# Akkucheck.net
KiCad netlist of a schematic drawn in EAGLE
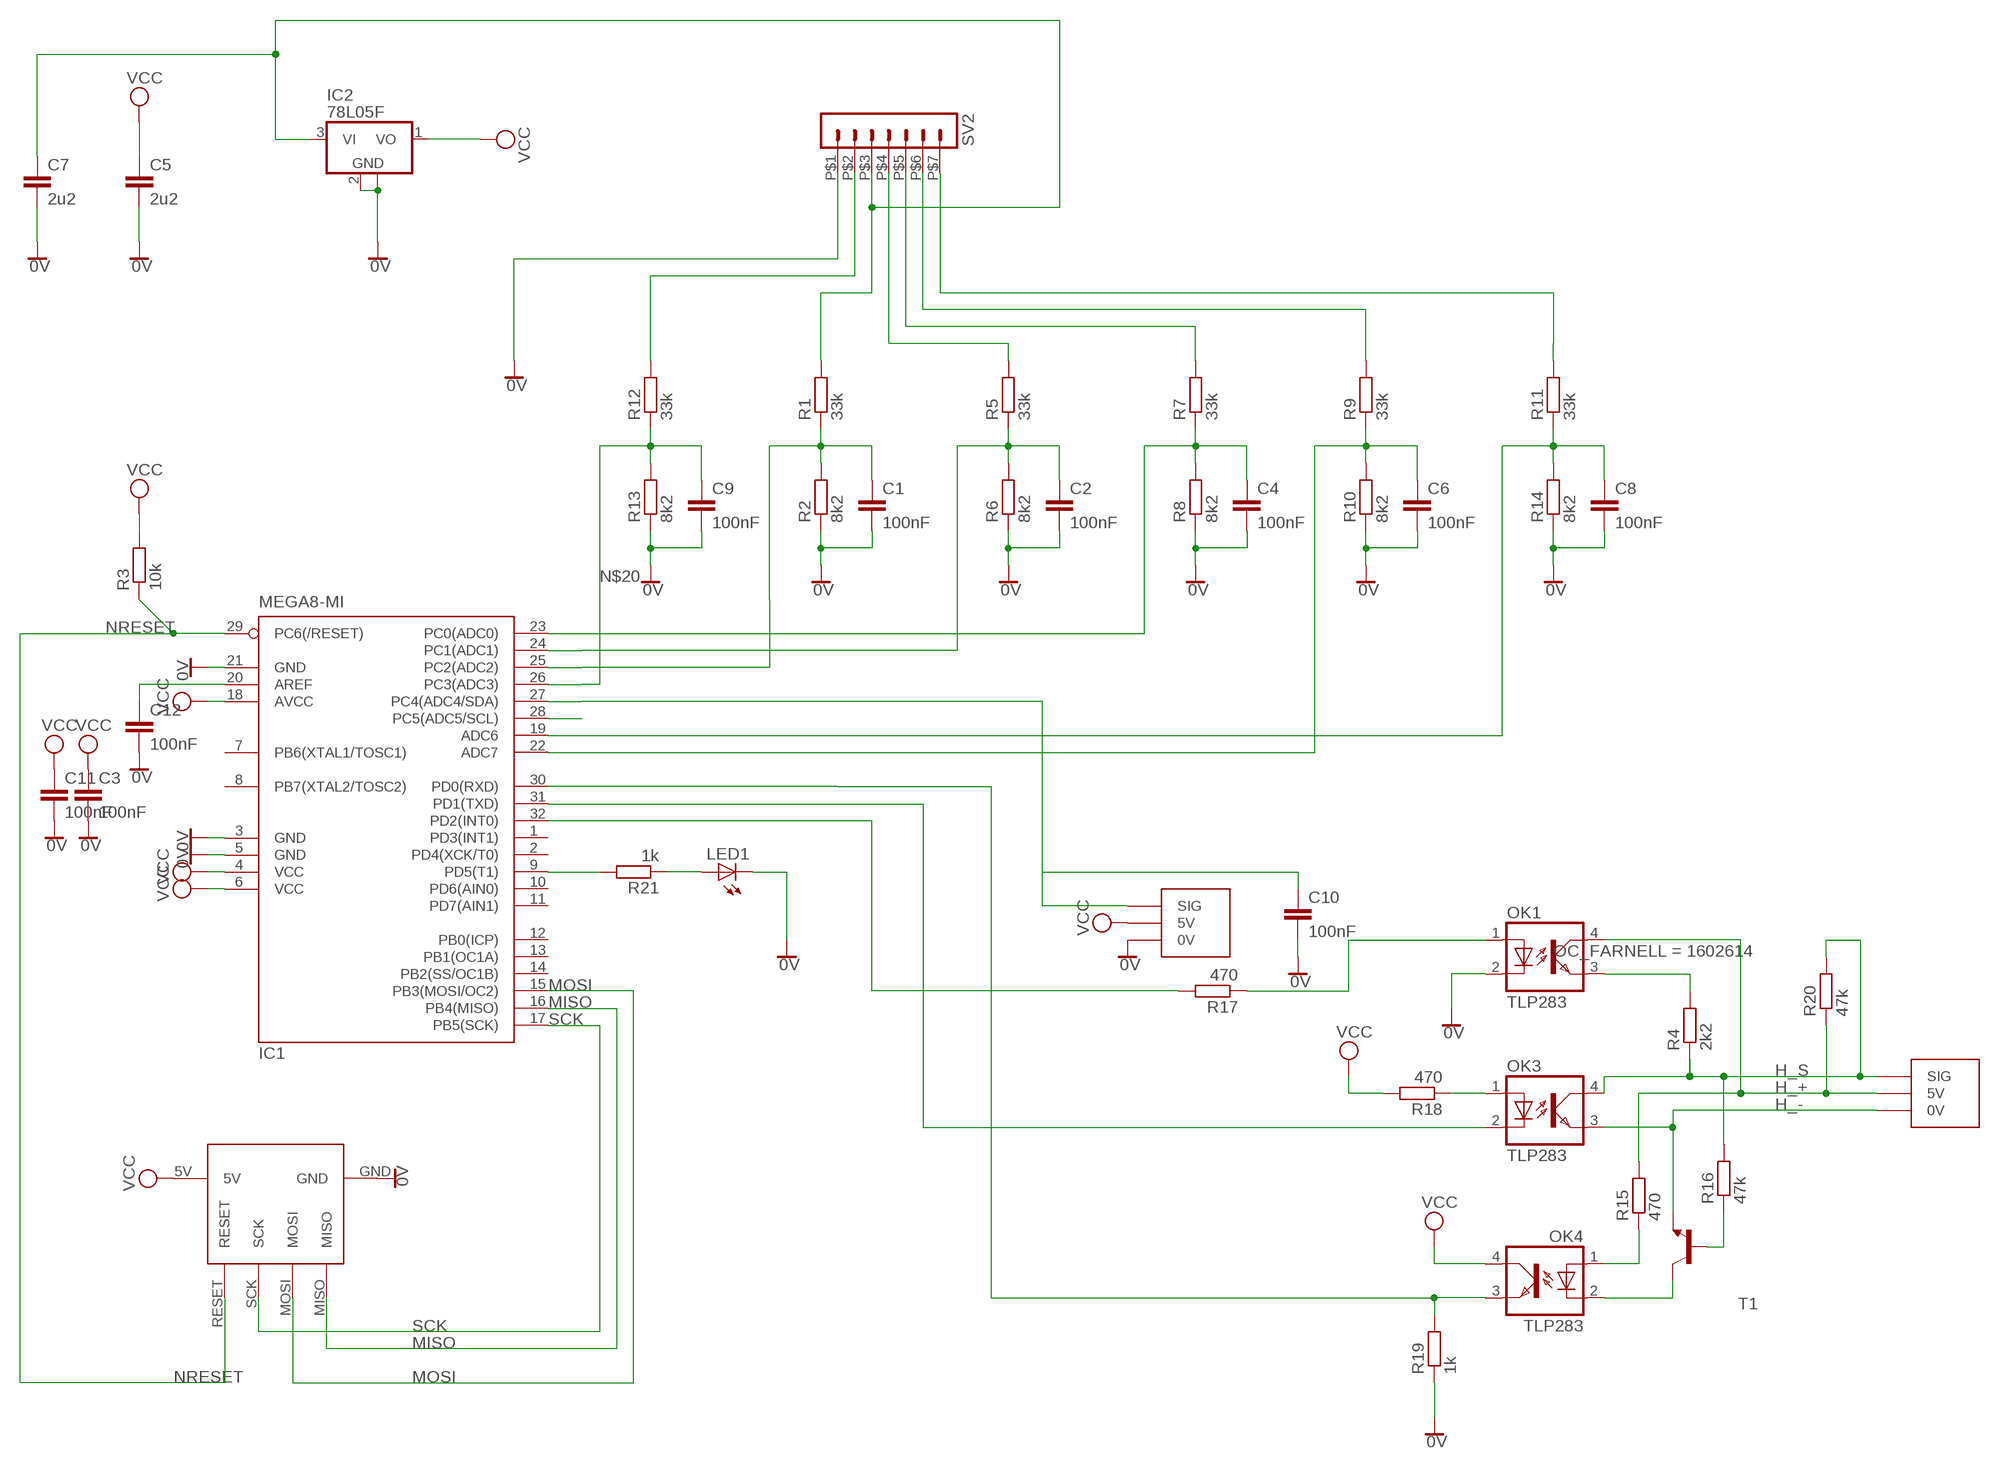
[diagram p0: schematic, sheet 1]

(export (version "E")
  (design (tool "Eeschema 10.0.6"))
  (components
    (comp (ref "C1")
      (value "100nF")
      (footprint "eagle-import:C0402")
      (fields (field (name "MF") "AVX") (field (name "MPN") "04023C104KAT2A"))
      (libsource (lib "eagle-import") (part "C-EUC0402"))
    )
    (comp (ref "C2")
      (value "100nF")
      (footprint "eagle-import:C0402")
      (fields (field (name "MF") "AVX") (field (name "MPN") "04023C104KAT2A"))
      (libsource (lib "eagle-import") (part "C-EUC0402"))
    )
    (comp (ref "C3")
      (value "100nF")
      (footprint "eagle-import:C0402")
      (fields (field (name "MF") "AVX") (field (name "MPN") "04023C104KAT2A"))
      (libsource (lib "eagle-import") (part "C-EUC0402"))
    )
    (comp (ref "C4")
      (value "100nF")
      (footprint "eagle-import:C0402")
      (fields (field (name "MF") "AVX") (field (name "MPN") "04023C104KAT2A"))
      (libsource (lib "eagle-import") (part "C-EUC0402"))
    )
    (comp (ref "C5")
      (value "2u2")
      (footprint "eagle-import:C0805")
      (fields (field (name "MF") "MULTICOMP") (field (name "MPN") "MC0805B225K250CT"))
      (libsource (lib "eagle-import") (part "C-EUC0805"))
    )
    (comp (ref "C6")
      (value "100nF")
      (footprint "eagle-import:C0402")
      (fields (field (name "MF") "AVX") (field (name "MPN") "04023C104KAT2A"))
      (libsource (lib "eagle-import") (part "C-EUC0402"))
    )
    (comp (ref "C7")
      (value "2u2")
      (footprint "eagle-import:C0805")
      (fields (field (name "MF") "MULTICOMP") (field (name "MPN") "MC0805B225K250CT"))
      (libsource (lib "eagle-import") (part "C-EUC0805"))
    )
    (comp (ref "C8")
      (value "100nF")
      (footprint "eagle-import:C0402")
      (fields (field (name "MF") "AVX") (field (name "MPN") "04023C104KAT2A"))
      (libsource (lib "eagle-import") (part "C-EUC0402"))
    )
    (comp (ref "C9")
      (value "100nF")
      (footprint "eagle-import:C0402")
      (fields (field (name "MF") "AVX") (field (name "MPN") "04023C104KAT2A"))
      (libsource (lib "eagle-import") (part "C-EUC0402"))
    )
    (comp (ref "C10")
      (value "100nF")
      (footprint "eagle-import:C0402")
      (fields (field (name "MF") "AVX") (field (name "MPN") "04023C104KAT2A"))
      (libsource (lib "eagle-import") (part "C-EUC0402"))
    )
    (comp (ref "C11")
      (value "100nF")
      (footprint "eagle-import:C0402")
      (fields (field (name "MF") "AVX") (field (name "MPN") "04023C104KAT2A"))
      (libsource (lib "eagle-import") (part "C-EUC0402"))
    )
    (comp (ref "C12")
      (value "100nF")
      (footprint "eagle-import:C0402")
      (fields (field (name "MF") "AVX") (field (name "MPN") "04023C104KAT2A"))
      (libsource (lib "eagle-import") (part "C-EUC0402"))
    )
    (comp (ref "IC1")
      (value "MEGA8-MI")
      (footprint "eagle-import:MLF32")
      (fields (field (name "MPN") "ATMEGA88PA-MU") (field (name "MF") "ATMEL"))
      (libsource (lib "eagle-import") (part "MEGA8-MI"))
    )
    (comp (ref "IC2")
      (value "78L05F")
      (footprint "eagle-import:SOT89")
      (fields (field (name "MF") "STMICROELECTRONICS") (field (name "MPN") "L78L05ABUTR"))
      (libsource (lib "eagle-import") (part "78LF05"))
    )
    (comp (ref "IN1")
      (value "3-WIRE_CONNWIRE")
      (footprint "eagle-import:3WIRE_CONN")
      (libsource (lib "eagle-import") (part "3-WIRE_CONNWIRE"))
    )
    (comp (ref "IN3")
      (value "3-WIRE_CONNWIRE")
      (footprint "eagle-import:3WIRE_CONN")
      (libsource (lib "eagle-import") (part "3-WIRE_CONNWIRE"))
    )
    (comp (ref "LED1")
      (value "LEDCHIPLED_0603")
      (footprint "eagle-import:CHIPLED_0603")
      (libsource (lib "eagle-import") (part "LEDCHIPLED_0603"))
    )
    (comp (ref "OK1")
      (value "TLP283")
      (footprint "eagle-import:MINI-FLAT-4")
      (fields
        (field (name "OC_FARNELL") "unknown")
        (field (name "MF") "AVAGO TECHNOLOGIES")
        (field (name "MPN") "ACPL-217-500E")
        (field (name "OC_FARNELL_1") "1602614")
      )
      (libsource (lib "eagle-import") (part "TLP283"))
    )
    (comp (ref "OK3")
      (value "TLP283")
      (footprint "eagle-import:MINI-FLAT-4")
      (fields
        (field (name "MF") "AVAGO TECHNOLOGIES")
        (field (name "MPN") "ACPL-217-500E")
        (field (name "OC_FARNELL") "1602614")
      )
      (libsource (lib "eagle-import") (part "TLP283"))
    )
    (comp (ref "OK4")
      (value "TLP283")
      (footprint "eagle-import:MINI-FLAT-4")
      (fields
        (field (name "MF") "AVAGO TECHNOLOGIES")
        (field (name "MPN") "ACPL-217-500E")
        (field (name "OC_FARNELL") "1602614")
      )
      (libsource (lib "eagle-import") (part "TLP283"))
    )
    (comp (ref "R1")
      (value "33k")
      (footprint "eagle-import:R0402")
      (fields (field (name "MF") "TE CONNECTIVITY") (field (name "MPN") "CRG0402F33K"))
      (libsource (lib "eagle-import") (part "R-EU_R0402"))
    )
    (comp (ref "R2")
      (value "8k2")
      (footprint "eagle-import:R0402")
      (fields (field (name "MF") "TE CONNECTIVITY") (field (name "MPN") "CRG0402F8K2"))
      (libsource (lib "eagle-import") (part "R-EU_R0402"))
    )
    (comp (ref "R3")
      (value "10k")
      (footprint "eagle-import:R0402")
      (fields (field (name "MF") "VISHAY DRALORIC") (field (name "MPN") "CRCW040210K0FKEAHP"))
      (libsource (lib "eagle-import") (part "R-EU_R0402"))
    )
    (comp (ref "R4")
      (value "2k2")
      (footprint "eagle-import:R0402")
      (fields (field (name "MF") "PANASONIC ELECTRONIC COMPONENTS") (field (name "MPN") "ERJ2GEJ222X"))
      (libsource (lib "eagle-import") (part "R-EU_R0402"))
    )
    (comp (ref "R5")
      (value "33k")
      (footprint "eagle-import:R0402")
      (fields (field (name "MF") "TE CONNECTIVITY") (field (name "MPN") "CRG0402F33K"))
      (libsource (lib "eagle-import") (part "R-EU_R0402"))
    )
    (comp (ref "R6")
      (value "8k2")
      (footprint "eagle-import:R0402")
      (fields (field (name "MF") "TE CONNECTIVITY") (field (name "MPN") "CRG0402F8K2"))
      (libsource (lib "eagle-import") (part "R-EU_R0402"))
    )
    (comp (ref "R7")
      (value "33k")
      (footprint "eagle-import:R0402")
      (fields (field (name "MF") "TE CONNECTIVITY") (field (name "MPN") "CRG0402F33K"))
      (libsource (lib "eagle-import") (part "R-EU_R0402"))
    )
    (comp (ref "R8")
      (value "8k2")
      (footprint "eagle-import:R0402")
      (fields (field (name "MF") "TE CONNECTIVITY") (field (name "MPN") "CRG0402F8K2"))
      (libsource (lib "eagle-import") (part "R-EU_R0402"))
    )
    (comp (ref "R9")
      (value "33k")
      (footprint "eagle-import:R0402")
      (fields (field (name "MF") "TE CONNECTIVITY") (field (name "MPN") "CRG0402F33K"))
      (libsource (lib "eagle-import") (part "R-EU_R0402"))
    )
    (comp (ref "R10")
      (value "8k2")
      (footprint "eagle-import:R0402")
      (fields (field (name "MF") "TE CONNECTIVITY") (field (name "MPN") "CRG0402F8K2"))
      (libsource (lib "eagle-import") (part "R-EU_R0402"))
    )
    (comp (ref "R11")
      (value "33k")
      (footprint "eagle-import:R0402")
      (fields (field (name "MF") "TE CONNECTIVITY") (field (name "MPN") "CRG0402F33K"))
      (libsource (lib "eagle-import") (part "R-EU_R0402"))
    )
    (comp (ref "R12")
      (value "33k")
      (footprint "eagle-import:R0402")
      (fields (field (name "MF") "TE CONNECTIVITY") (field (name "MPN") "CRG0402F33K"))
      (libsource (lib "eagle-import") (part "R-EU_R0402"))
    )
    (comp (ref "R13")
      (value "8k2")
      (footprint "eagle-import:R0402")
      (fields (field (name "MF") "TE CONNECTIVITY") (field (name "MPN") "CRG0402F8K2"))
      (libsource (lib "eagle-import") (part "R-EU_R0402"))
    )
    (comp (ref "R14")
      (value "8k2")
      (footprint "eagle-import:R0402")
      (fields (field (name "MF") "TE CONNECTIVITY") (field (name "MPN") "CRG0402F8K2"))
      (libsource (lib "eagle-import") (part "R-EU_R0402"))
    )
    (comp (ref "R15")
      (value "470")
      (footprint "eagle-import:R0402")
      (fields (field (name "MF") "PANASONIC ELECTRONIC COMPONENTS") (field (name "MPN") "ERJ2GEJ470X"))
      (libsource (lib "eagle-import") (part "R-EU_R0402"))
    )
    (comp (ref "R16")
      (value "47k")
      (footprint "eagle-import:R0402")
      (fields (field (name "MF") "PANASONIC ELECTRONIC COMPONENTS") (field (name "MPN") "ERJ2GEJ473X"))
      (libsource (lib "eagle-import") (part "R-EU_R0402"))
    )
    (comp (ref "R17")
      (value "470")
      (footprint "eagle-import:R0402")
      (fields (field (name "MF") "PANASONIC ELECTRONIC COMPONENTS") (field (name "MPN") "ERJ2GEJ470X"))
      (libsource (lib "eagle-import") (part "R-EU_R0402"))
    )
    (comp (ref "R18")
      (value "470")
      (footprint "eagle-import:R0402")
      (fields (field (name "MF") "PANASONIC ELECTRONIC COMPONENTS") (field (name "MPN") "ERJ2GEJ470X"))
      (libsource (lib "eagle-import") (part "R-EU_R0402"))
    )
    (comp (ref "R19")
      (value "1k")
      (footprint "eagle-import:R0402")
      (fields (field (name "MF") "PANASONIC ELECTRONIC COMPONENTS") (field (name "MPN") "ERJ2GEJ102X"))
      (libsource (lib "eagle-import") (part "R-EU_R0402"))
    )
    (comp (ref "R20")
      (value "47k")
      (footprint "eagle-import:R0402")
      (fields (field (name "MF") "PANASONIC ELECTRONIC COMPONENTS") (field (name "MPN") "ERJ2GEJ473X"))
      (libsource (lib "eagle-import") (part "R-EU_R0402"))
    )
    (comp (ref "R21")
      (value "1k")
      (footprint "eagle-import:R0402")
      (fields (field (name "MF") "PANASONIC ELECTRONIC COMPONENTS") (field (name "MPN") "ERJ2GEJ102X"))
      (libsource (lib "eagle-import") (part "R-EU_R0402"))
    )
    (comp (ref "SV2")
      (value "MA07-1_SMD")
      (footprint "eagle-import:MA07-1_SMD")
      (libsource (lib "eagle-import") (part "MA07-1_SMD"))
    )
    (comp (ref "T1")
      (value "BC817-16-NPN-SOT23-BEC")
      (footprint "eagle-import:SOT23-BEC")
      (fields (field (name "MF") "NXP") (field (name "MPN") "BC817,215"))
      (libsource (lib "eagle-import") (part "-NPN-SOT23-BECBC817-16"))
    )
    (comp (ref "U$1")
      (value "ISPSMD")
      (footprint "eagle-import:ISP_SMD")
      (libsource (lib "eagle-import") (part "ISPSMD"))
    )
  )
  (nets
    (net (code "1") (name "/H_+") (class "Default")
      (node (ref "IN3") (pin "5V") (pinfunction "5V_5V") (pintype "bidirectional"))
      (node (ref "OK1") (pin "4") (pinfunction "COL_4") (pintype "passive"))
      (node (ref "R15") (pin "2") (pinfunction "2_2") (pintype "passive"))
      (node (ref "R20") (pin "1") (pinfunction "1_1") (pintype "passive"))
    )
    (net (code "2") (name "/H_-") (class "Default")
      (node (ref "IN3") (pin "0V") (pinfunction "0V_0V") (pintype "bidirectional"))
      (node (ref "OK3") (pin "3") (pinfunction "EMIT_3") (pintype "passive"))
      (node (ref "T1") (pin "E") (pinfunction "E_E") (pintype "passive"))
    )
    (net (code "3") (name "/H_S") (class "Default")
      (node (ref "IN3") (pin "SIG") (pinfunction "SIG_SIG") (pintype "bidirectional"))
      (node (ref "OK3") (pin "4") (pinfunction "COL_4") (pintype "passive"))
      (node (ref "R16") (pin "2") (pinfunction "2_2") (pintype "passive"))
      (node (ref "R20") (pin "2") (pinfunction "2_2") (pintype "passive"))
      (node (ref "R4") (pin "1") (pinfunction "1_1") (pintype "passive"))
    )
    (net (code "4") (name "/MISO") (class "Default")
      (node (ref "IC1") (pin "16") (pinfunction "PB4(MISO)_16") (pintype "bidirectional"))
      (node (ref "U$1") (pin "MISO") (pinfunction "MISO_MISO") (pintype "bidirectional"))
    )
    (net (code "5") (name "/MOSI") (class "Default")
      (node (ref "IC1") (pin "15") (pinfunction "PB3(MOSI/OC2)_15") (pintype "bidirectional"))
      (node (ref "U$1") (pin "MOSI") (pinfunction "MOSI_MOSI") (pintype "bidirectional"))
    )
    (net (code "6") (name "/N$20") (class "Default")
      (node (ref "C9") (pin "1") (pinfunction "1_1") (pintype "passive"))
      (node (ref "IC1") (pin "26") (pinfunction "PC3(ADC3)_26") (pintype "bidirectional"))
      (node (ref "R12") (pin "1") (pinfunction "1_1") (pintype "passive"))
      (node (ref "R13") (pin "2") (pinfunction "2_2") (pintype "passive"))
    )
    (net (code "7") (name "/NRESET") (class "Default")
      (node (ref "IC1") (pin "29") (pinfunction "PC6(/RESET)_29") (pintype "bidirectional"))
      (node (ref "R3") (pin "1") (pinfunction "1_1") (pintype "passive"))
      (node (ref "U$1") (pin "RESET") (pinfunction "RESET_RESET") (pintype "bidirectional"))
    )
    (net (code "8") (name "/SCK") (class "Default")
      (node (ref "IC1") (pin "17") (pinfunction "PB5(SCK)_17") (pintype "bidirectional"))
      (node (ref "U$1") (pin "SCK") (pinfunction "SCK_SCK") (pintype "bidirectional"))
    )
    (net (code "9") (name "0V") (class "Default")
      (node (ref "C1") (pin "2") (pinfunction "2_2") (pintype "passive"))
      (node (ref "C10") (pin "2") (pinfunction "2_2") (pintype "passive"))
      (node (ref "C11") (pin "2") (pinfunction "2_2") (pintype "passive"))
      (node (ref "C12") (pin "2") (pinfunction "2_2") (pintype "passive"))
      (node (ref "C2") (pin "2") (pinfunction "2_2") (pintype "passive"))
      (node (ref "C3") (pin "2") (pinfunction "2_2") (pintype "passive"))
      (node (ref "C4") (pin "2") (pinfunction "2_2") (pintype "passive"))
      (node (ref "C5") (pin "2") (pinfunction "2_2") (pintype "passive"))
      (node (ref "C6") (pin "2") (pinfunction "2_2") (pintype "passive"))
      (node (ref "C7") (pin "2") (pinfunction "2_2") (pintype "passive"))
      (node (ref "C8") (pin "2") (pinfunction "2_2") (pintype "passive"))
      (node (ref "C9") (pin "2") (pinfunction "2_2") (pintype "passive"))
      (node (ref "IC1") (pin "21") (pinfunction "GND_21") (pintype "power_in"))
      (node (ref "IC1") (pin "3") (pinfunction "GND_3") (pintype "power_in"))
      (node (ref "IC1") (pin "5") (pinfunction "GND_5") (pintype "power_in"))
      (node (ref "IC2") (pin "2") (pinfunction "GND_2") (pintype "passive"))
      (node (ref "IC2") (pin "2@1") (pinfunction "GND_2@1") (pintype "passive"))
      (node (ref "IN1") (pin "0V") (pinfunction "0V_0V") (pintype "bidirectional"))
      (node (ref "LED1") (pin "C") (pinfunction "C_C") (pintype "passive"))
      (node (ref "OK1") (pin "2") (pinfunction "C_2") (pintype "passive"))
      (node (ref "R10") (pin "1") (pinfunction "1_1") (pintype "passive"))
      (node (ref "R13") (pin "1") (pinfunction "1_1") (pintype "passive"))
      (node (ref "R14") (pin "1") (pinfunction "1_1") (pintype "passive"))
      (node (ref "R19") (pin "1") (pinfunction "1_1") (pintype "passive"))
      (node (ref "R2") (pin "1") (pinfunction "1_1") (pintype "passive"))
      (node (ref "R6") (pin "1") (pinfunction "1_1") (pintype "passive"))
      (node (ref "R8") (pin "1") (pinfunction "1_1") (pintype "passive"))
      (node (ref "SV2") (pin "P$1") (pinfunction "1_P$1") (pintype "passive"))
      (node (ref "U$1") (pin "GND") (pinfunction "GND_GND") (pintype "bidirectional"))
    )
    (net (code "10") (name "Net-(IC1-ADC6)") (class "Default")
      (node (ref "C8") (pin "1") (pinfunction "1_1") (pintype "passive"))
      (node (ref "IC1") (pin "19") (pinfunction "ADC6_19") (pintype "bidirectional"))
      (node (ref "R11") (pin "1") (pinfunction "1_1") (pintype "passive"))
      (node (ref "R14") (pin "2") (pinfunction "2_2") (pintype "passive"))
    )
    (net (code "11") (name "Net-(IC1-ADC7)") (class "Default")
      (node (ref "C6") (pin "1") (pinfunction "1_1") (pintype "passive"))
      (node (ref "IC1") (pin "22") (pinfunction "ADC7_22") (pintype "bidirectional"))
      (node (ref "R10") (pin "2") (pinfunction "2_2") (pintype "passive"))
      (node (ref "R9") (pin "1") (pinfunction "1_1") (pintype "passive"))
    )
    (net (code "12") (name "Net-(IC1-AREF)") (class "Default")
      (node (ref "C12") (pin "1") (pinfunction "1_1") (pintype "passive"))
      (node (ref "IC1") (pin "20") (pinfunction "AREF_20") (pintype "passive"))
    )
    (net (code "13") (name "Net-(IC1-PC0(ADC0))") (class "Default")
      (node (ref "C4") (pin "1") (pinfunction "1_1") (pintype "passive"))
      (node (ref "IC1") (pin "23") (pinfunction "PC0(ADC0)_23") (pintype "bidirectional"))
      (node (ref "R7") (pin "1") (pinfunction "1_1") (pintype "passive"))
      (node (ref "R8") (pin "2") (pinfunction "2_2") (pintype "passive"))
    )
    (net (code "14") (name "Net-(IC1-PC1(ADC1))") (class "Default")
      (node (ref "C2") (pin "1") (pinfunction "1_1") (pintype "passive"))
      (node (ref "IC1") (pin "24") (pinfunction "PC1(ADC1)_24") (pintype "bidirectional"))
      (node (ref "R5") (pin "1") (pinfunction "1_1") (pintype "passive"))
      (node (ref "R6") (pin "2") (pinfunction "2_2") (pintype "passive"))
    )
    (net (code "15") (name "Net-(IC1-PC2(ADC2))") (class "Default")
      (node (ref "C1") (pin "1") (pinfunction "1_1") (pintype "passive"))
      (node (ref "IC1") (pin "25") (pinfunction "PC2(ADC2)_25") (pintype "bidirectional"))
      (node (ref "R1") (pin "1") (pinfunction "1_1") (pintype "passive"))
      (node (ref "R2") (pin "2") (pinfunction "2_2") (pintype "passive"))
    )
    (net (code "16") (name "Net-(IC1-PC4(ADC4{slash}SDA))") (class "Default")
      (node (ref "C10") (pin "1") (pinfunction "1_1") (pintype "passive"))
      (node (ref "IC1") (pin "27") (pinfunction "PC4(ADC4/SDA)_27") (pintype "bidirectional"))
      (node (ref "IN1") (pin "SIG") (pinfunction "SIG_SIG") (pintype "bidirectional"))
    )
    (net (code "17") (name "Net-(IC1-PD0(RXD))") (class "Default")
      (node (ref "IC1") (pin "30") (pinfunction "PD0(RXD)_30") (pintype "bidirectional"))
      (node (ref "OK4") (pin "3") (pinfunction "EMIT_3") (pintype "passive"))
      (node (ref "R19") (pin "2") (pinfunction "2_2") (pintype "passive"))
    )
    (net (code "18") (name "Net-(IC1-PD1(TXD))") (class "Default")
      (node (ref "IC1") (pin "31") (pinfunction "PD1(TXD)_31") (pintype "bidirectional"))
      (node (ref "OK3") (pin "2") (pinfunction "C_2") (pintype "passive"))
    )
    (net (code "19") (name "Net-(IC1-PD2(INT0))") (class "Default")
      (node (ref "IC1") (pin "32") (pinfunction "PD2(INT0)_32") (pintype "bidirectional"))
      (node (ref "R17") (pin "2") (pinfunction "2_2") (pintype "passive"))
    )
    (net (code "20") (name "Net-(IC1-PD5(T1))") (class "Default")
      (node (ref "IC1") (pin "9") (pinfunction "PD5(T1)_9") (pintype "bidirectional"))
      (node (ref "R21") (pin "2") (pinfunction "2_2") (pintype "passive"))
    )
    (net (code "21") (name "Net-(IC2-VI)") (class "Default")
      (node (ref "C7") (pin "1") (pinfunction "1_1") (pintype "passive"))
      (node (ref "IC2") (pin "3") (pinfunction "VI_3") (pintype "input"))
      (node (ref "R1") (pin "2") (pinfunction "2_2") (pintype "passive"))
      (node (ref "SV2") (pin "P$3") (pinfunction "3_P$3") (pintype "passive"))
    )
    (net (code "22") (name "Net-(LED1-PadA)") (class "Default")
      (node (ref "LED1") (pin "A") (pinfunction "A_A") (pintype "passive"))
      (node (ref "R21") (pin "1") (pinfunction "1_1") (pintype "passive"))
    )
    (net (code "23") (name "Net-(OK1-A)") (class "Default")
      (node (ref "OK1") (pin "1") (pinfunction "A_1") (pintype "passive"))
      (node (ref "R17") (pin "1") (pinfunction "1_1") (pintype "passive"))
    )
    (net (code "24") (name "Net-(OK1-EMIT)") (class "Default")
      (node (ref "OK1") (pin "3") (pinfunction "EMIT_3") (pintype "passive"))
      (node (ref "R4") (pin "2") (pinfunction "2_2") (pintype "passive"))
    )
    (net (code "25") (name "Net-(OK3-A)") (class "Default")
      (node (ref "OK3") (pin "1") (pinfunction "A_1") (pintype "passive"))
      (node (ref "R18") (pin "1") (pinfunction "1_1") (pintype "passive"))
    )
    (net (code "26") (name "Net-(OK4-A)") (class "Default")
      (node (ref "OK4") (pin "1") (pinfunction "A_1") (pintype "passive"))
      (node (ref "R15") (pin "1") (pinfunction "1_1") (pintype "passive"))
    )
    (net (code "27") (name "Net-(OK4-C)") (class "Default")
      (node (ref "OK4") (pin "2") (pinfunction "C_2") (pintype "passive"))
      (node (ref "T1") (pin "C") (pinfunction "C_C") (pintype "passive"))
    )
    (net (code "28") (name "Net-(R16-Pad1)") (class "Default")
      (node (ref "R16") (pin "1") (pinfunction "1_1") (pintype "passive"))
      (node (ref "T1") (pin "B") (pinfunction "B_B") (pintype "passive"))
    )
    (net (code "29") (name "Net-(SV2-2)") (class "Default")
      (node (ref "R12") (pin "2") (pinfunction "2_2") (pintype "passive"))
      (node (ref "SV2") (pin "P$2") (pinfunction "2_P$2") (pintype "passive"))
    )
    (net (code "30") (name "Net-(SV2-4)") (class "Default")
      (node (ref "R5") (pin "2") (pinfunction "2_2") (pintype "passive"))
      (node (ref "SV2") (pin "P$4") (pinfunction "4_P$4") (pintype "passive"))
    )
    (net (code "31") (name "Net-(SV2-5)") (class "Default")
      (node (ref "R7") (pin "2") (pinfunction "2_2") (pintype "passive"))
      (node (ref "SV2") (pin "P$5") (pinfunction "5_P$5") (pintype "passive"))
    )
    (net (code "32") (name "Net-(SV2-6)") (class "Default")
      (node (ref "R9") (pin "2") (pinfunction "2_2") (pintype "passive"))
      (node (ref "SV2") (pin "P$6") (pinfunction "6_P$6") (pintype "passive"))
    )
    (net (code "33") (name "Net-(SV2-7)") (class "Default")
      (node (ref "R11") (pin "2") (pinfunction "2_2") (pintype "passive"))
      (node (ref "SV2") (pin "P$7") (pinfunction "7_P$7") (pintype "passive"))
    )
    (net (code "34") (name "VCC") (class "Default")
      (node (ref "C11") (pin "1") (pinfunction "1_1") (pintype "passive"))
      (node (ref "C3") (pin "1") (pinfunction "1_1") (pintype "passive"))
      (node (ref "C5") (pin "1") (pinfunction "1_1") (pintype "passive"))
      (node (ref "IC1") (pin "18") (pinfunction "AVCC_18") (pintype "power_in"))
      (node (ref "IC1") (pin "4") (pinfunction "VCC_4") (pintype "power_in"))
      (node (ref "IC1") (pin "6") (pinfunction "VCC_6") (pintype "power_in"))
      (node (ref "IC2") (pin "1") (pinfunction "VO_1") (pintype "passive"))
      (node (ref "IN1") (pin "5V") (pinfunction "5V_5V") (pintype "bidirectional"))
      (node (ref "OK4") (pin "4") (pinfunction "COL_4") (pintype "passive"))
      (node (ref "R18") (pin "2") (pinfunction "2_2") (pintype "passive"))
      (node (ref "R3") (pin "2") (pinfunction "2_2") (pintype "passive"))
      (node (ref "U$1") (pin "5V") (pinfunction "5V_5V") (pintype "bidirectional"))
    )
    (net (code "35") (name "unconnected-(IC1-PB0(ICP)-Pad12)") (class "Default")
      (node (ref "IC1") (pin "12") (pinfunction "PB0(ICP)_12") (pintype "bidirectional"))
    )
    (net (code "36") (name "unconnected-(IC1-PB1(OC1A)-Pad13)") (class "Default")
      (node (ref "IC1") (pin "13") (pinfunction "PB1(OC1A)_13") (pintype "bidirectional"))
    )
    (net (code "37") (name "unconnected-(IC1-PB2(SS{slash}OC1B)-Pad14)") (class "Default")
      (node (ref "IC1") (pin "14") (pinfunction "PB2(SS/OC1B)_14") (pintype "bidirectional"))
    )
    (net (code "38") (name "unconnected-(IC1-PB6(XTAL1{slash}TOSC1)-Pad7)") (class "Default")
      (node (ref "IC1") (pin "7") (pinfunction "PB6(XTAL1/TOSC1)_7") (pintype "bidirectional"))
    )
    (net (code "39") (name "unconnected-(IC1-PB7(XTAL2{slash}TOSC2)-Pad8)") (class "Default")
      (node (ref "IC1") (pin "8") (pinfunction "PB7(XTAL2/TOSC2)_8") (pintype "bidirectional"))
    )
    (net (code "40") (name "unconnected-(IC1-PC5(ADC5{slash}SCL)-Pad28)") (class "Default")
      (node (ref "IC1") (pin "28") (pinfunction "PC5(ADC5/SCL)_28") (pintype "bidirectional"))
    )
    (net (code "41") (name "unconnected-(IC1-PD3(INT1)-Pad1)") (class "Default")
      (node (ref "IC1") (pin "1") (pinfunction "PD3(INT1)_1") (pintype "bidirectional"))
    )
    (net (code "42") (name "unconnected-(IC1-PD4(XCK{slash}T0)-Pad2)") (class "Default")
      (node (ref "IC1") (pin "2") (pinfunction "PD4(XCK/T0)_2") (pintype "bidirectional"))
    )
    (net (code "43") (name "unconnected-(IC1-PD6(AIN0)-Pad10)") (class "Default")
      (node (ref "IC1") (pin "10") (pinfunction "PD6(AIN0)_10") (pintype "bidirectional"))
    )
    (net (code "44") (name "unconnected-(IC1-PD7(AIN1)-Pad11)") (class "Default")
      (node (ref "IC1") (pin "11") (pinfunction "PD7(AIN1)_11") (pintype "bidirectional"))
    )
  )
)
